# Reflow_Panel_Rev_F.net
KiCad netlist of a schematic drawn in EAGLE
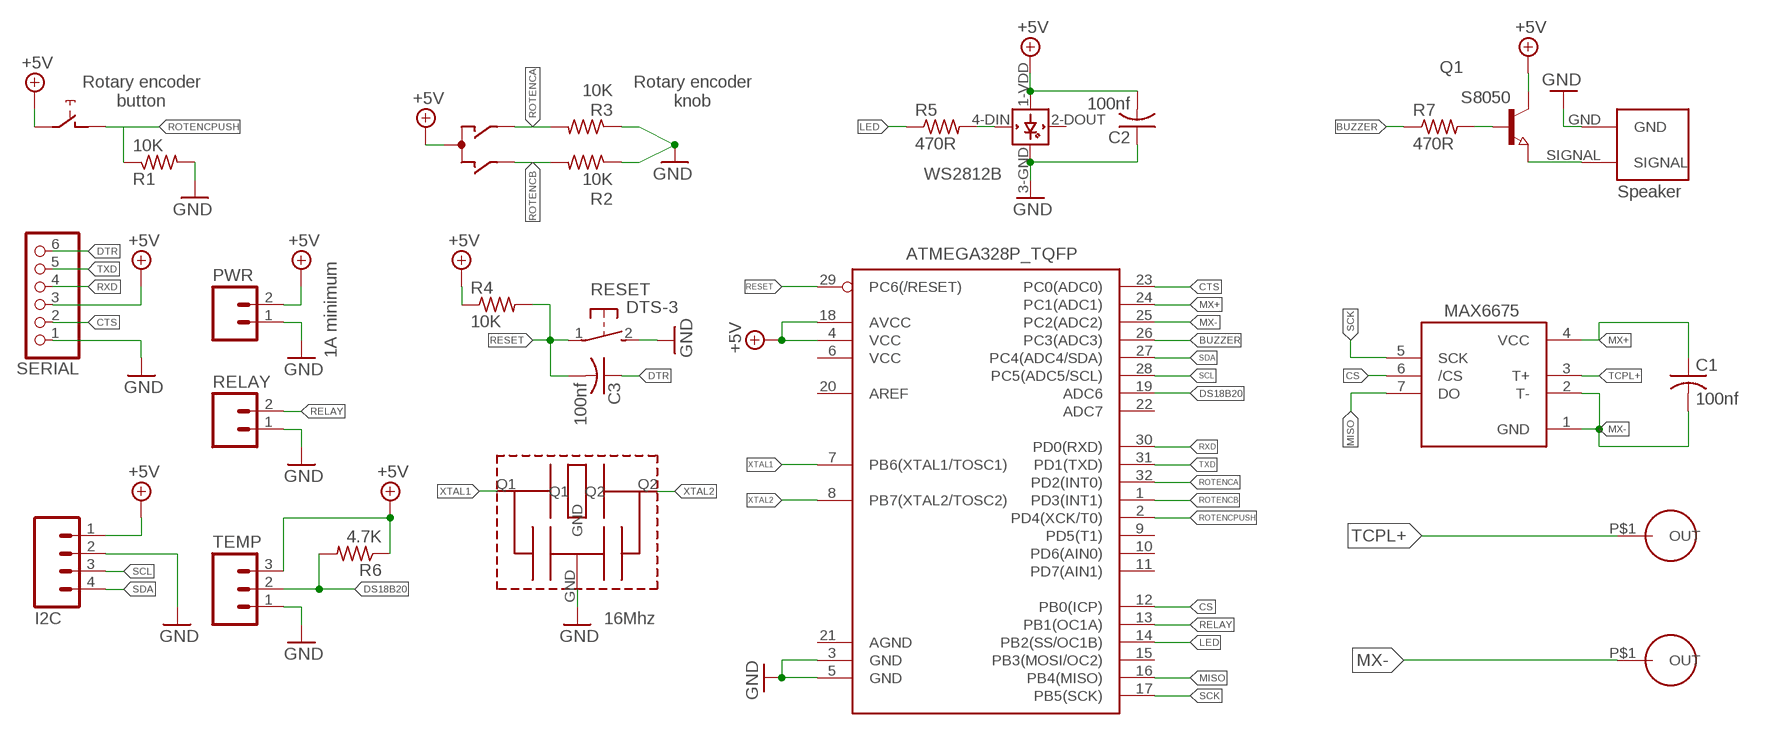
[diagram p0: schematic, sheet 1]

(export (version "E")
  (design (tool "Eeschema 10.0.6"))
  (components
    (comp (ref "C1")
      (value "100nf")
      (footprint "eagle-import:C0805")
      (libsource (lib "eagle-import") (part "C-USC0805"))
    )
    (comp (ref "C2")
      (value "100nf")
      (footprint "eagle-import:C0805")
      (libsource (lib "eagle-import") (part "C-USC0805"))
    )
    (comp (ref "C3")
      (value "100nf")
      (footprint "eagle-import:C0805")
      (libsource (lib "eagle-import") (part "C-USC0805"))
    )
    (comp (ref "I2C")
      (value "M04LOCK_LONGPADS")
      (footprint "eagle-import:1X04_LOCK_LONGPADS")
      (libsource (lib "eagle-import") (part "M04LOCK_LONGPADS"))
    )
    (comp (ref "IC2")
      (value "MAX6675")
      (footprint "eagle-import:SO08")
      (libsource (lib "eagle-import") (part "MAX6675"))
    )
    (comp (ref "L1")
      (value "WS2812B_")
      (footprint "eagle-import:WS2812B")
      (libsource (lib "eagle-import") (part "WS2812B_"))
    )
    (comp (ref "PWR")
      (value "M02LOCK")
      (footprint "eagle-import:1X02_LOCK")
      (libsource (lib "eagle-import") (part "M02LOCK"))
    )
    (comp (ref "Q1")
      (value "NPN-TRANSISTOR_SOT23")
      (footprint "eagle-import:SOT23")
      (libsource (lib "eagle-import") (part "NPN-TRANSISTOR_SOT23"))
    )
    (comp (ref "R1")
      (value "10K")
      (footprint "eagle-import:M0805")
      (libsource (lib "eagle-import") (part "R-US_M0805"))
    )
    (comp (ref "R2")
      (value "10K")
      (footprint "eagle-import:M0805")
      (libsource (lib "eagle-import") (part "R-US_M0805"))
    )
    (comp (ref "R3")
      (value "10K")
      (footprint "eagle-import:M0805")
      (libsource (lib "eagle-import") (part "R-US_M0805"))
    )
    (comp (ref "R4")
      (value "10K")
      (footprint "eagle-import:M0805")
      (libsource (lib "eagle-import") (part "R-US_M0805"))
    )
    (comp (ref "R5")
      (value "470R")
      (footprint "eagle-import:M0805")
      (libsource (lib "eagle-import") (part "R-US_M0805"))
    )
    (comp (ref "R6")
      (value "4.7K")
      (footprint "eagle-import:M0805")
      (libsource (lib "eagle-import") (part "R-US_M0805"))
    )
    (comp (ref "R7")
      (value "470R")
      (footprint "eagle-import:M0805")
      (libsource (lib "eagle-import") (part "R-US_M0805"))
    )
    (comp (ref "RELAY")
      (value "M02LOCK")
      (footprint "eagle-import:1X02_LOCK")
      (libsource (lib "eagle-import") (part "M02LOCK"))
    )
    (comp (ref "RESET")
      (value "DTS-3")
      (footprint "eagle-import:DTS-3")
      (libsource (lib "eagle-import") (part "DTS-3"))
    )
    (comp (ref "SERIAL")
      (value "PINHD-1X6LOCK")
      (footprint "eagle-import:1X06-BIGLOCK")
      (libsource (lib "eagle-import") (part "PINHD-1X6LOCK"))
    )
    (comp (ref "SW1")
      (value "EC12E_SW")
      (footprint "eagle-import:ALPS_EC12E_SW")
      (fields (field (name "MPN") "EC12E2424407"))
      (libsource (lib "eagle-import") (part "EC12E_SW"))
    )
    (comp (ref "TEMP")
      (value "M03LOCK")
      (footprint "eagle-import:1X03_LOCK")
      (libsource (lib "eagle-import") (part "M03LOCK"))
    )
    (comp (ref "U$1")
      (value "8.5MMSQUAREBUZZER")
      (footprint "eagle-import:8.5MMSQUAREBUZZER")
      (libsource (lib "eagle-import") (part "8.5MMSQUAREBUZZER"))
    )
    (comp (ref "U$2")
      (value "CSTCE16M0V53-R0")
      (footprint "eagle-import:CSTCE_V13C")
      (libsource (lib "eagle-import") (part "CSTCE16M0V53-R0"))
    )
    (comp (ref "U$3")
      (value "BANANAFEMAIL-10.8-5.7")
      (footprint "eagle-import:BANANAFEMALE-10.8-5.7")
      (libsource (lib "eagle-import") (part "BANANAFEMAIL-10.8-5.7"))
    )
    (comp (ref "U$4")
      (value "BANANAFEMAIL-10.8-5.7")
      (footprint "eagle-import:BANANAFEMALE-10.8-5.7")
      (libsource (lib "eagle-import") (part "BANANAFEMAIL-10.8-5.7"))
    )
    (comp (ref "U1")
      (value "ATMEGA328P_TQFP")
      (footprint "eagle-import:TQFP32-08")
      (libsource (lib "eagle-import") (part "ATMEGA328P_TQFP"))
    )
  )
  (nets
    (net (code "1") (name "+5V") (class "Default")
      (node (ref "C2") (pin "2") (pinfunction "2_2") (pintype "passive"))
      (node (ref "I2C") (pin "1") (pinfunction "1_1") (pintype "passive"))
      (node (ref "L1") (pin "1-VDD") (pinfunction "VDD_1-VDD") (pintype "bidirectional"))
      (node (ref "PWR") (pin "2") (pinfunction "2_2") (pintype "passive"))
      (node (ref "Q1") (pin "3") (pinfunction "C_3") (pintype "passive"))
      (node (ref "R4") (pin "1") (pinfunction "1_1") (pintype "passive"))
      (node (ref "R6") (pin "1") (pinfunction "1_1") (pintype "passive"))
      (node (ref "SERIAL") (pin "3") (pinfunction "3_3") (pintype "passive"))
      (node (ref "SW1") (pin "C") (pinfunction "C_C") (pintype "passive"))
      (node (ref "SW1") (pin "E") (pinfunction "2_E") (pintype "passive"))
      (node (ref "TEMP") (pin "3") (pinfunction "3_3") (pintype "passive"))
      (node (ref "U1") (pin "18") (pinfunction "AVCC_18") (pintype "bidirectional"))
      (node (ref "U1") (pin "4") (pinfunction "VCC_4") (pintype "bidirectional"))
    )
    (net (code "2") (name "BUZZER") (class "Default")
      (node (ref "R7") (pin "1") (pinfunction "1_1") (pintype "passive"))
      (node (ref "U1") (pin "26") (pinfunction "PC3(ADC3)_26") (pintype "bidirectional"))
    )
    (net (code "3") (name "CS") (class "Default")
      (node (ref "IC2") (pin "6") (pinfunction "/CS_6") (pintype "input"))
      (node (ref "U1") (pin "12") (pinfunction "PB0(ICP)_12") (pintype "bidirectional"))
    )
    (net (code "4") (name "CTS") (class "Default")
      (node (ref "SERIAL") (pin "2") (pinfunction "2_2") (pintype "passive"))
      (node (ref "U1") (pin "23") (pinfunction "PC0(ADC0)_23") (pintype "bidirectional"))
    )
    (net (code "5") (name "DS18B20") (class "Default")
      (node (ref "R6") (pin "2") (pinfunction "2_2") (pintype "passive"))
      (node (ref "TEMP") (pin "2") (pinfunction "2_2") (pintype "passive"))
      (node (ref "U1") (pin "19") (pinfunction "ADC6_19") (pintype "bidirectional"))
    )
    (net (code "6") (name "DTR") (class "Default")
      (node (ref "C3") (pin "1") (pinfunction "1_1") (pintype "passive"))
      (node (ref "SERIAL") (pin "6") (pinfunction "6_6") (pintype "passive"))
    )
    (net (code "7") (name "GND") (class "Default")
      (node (ref "C2") (pin "1") (pinfunction "1_1") (pintype "passive"))
      (node (ref "I2C") (pin "2") (pinfunction "2_2") (pintype "passive"))
      (node (ref "L1") (pin "3-GND") (pinfunction "GND_3-GND") (pintype "bidirectional"))
      (node (ref "PWR") (pin "1") (pinfunction "1_1") (pintype "passive"))
      (node (ref "R1") (pin "2") (pinfunction "2_2") (pintype "passive"))
      (node (ref "R2") (pin "1") (pinfunction "1_1") (pintype "passive"))
      (node (ref "R3") (pin "1") (pinfunction "1_1") (pintype "passive"))
      (node (ref "RELAY") (pin "1") (pinfunction "1_1") (pintype "passive"))
      (node (ref "RESET") (pin "2") (pinfunction "2_2") (pintype "passive"))
      (node (ref "SERIAL") (pin "1") (pinfunction "1_1") (pintype "passive"))
      (node (ref "TEMP") (pin "1") (pinfunction "1_1") (pintype "passive"))
      (node (ref "U$1") (pin "GND") (pinfunction "GND_GND") (pintype "bidirectional"))
      (node (ref "U$2") (pin "GND") (pinfunction "GND_GND") (pintype "bidirectional"))
      (node (ref "U1") (pin "3") (pinfunction "GND_3") (pintype "bidirectional"))
      (node (ref "U1") (pin "5") (pinfunction "GND_5") (pintype "bidirectional"))
    )
    (net (code "8") (name "LED") (class "Default")
      (node (ref "R5") (pin "1") (pinfunction "1_1") (pintype "passive"))
      (node (ref "U1") (pin "14") (pinfunction "PB2(SS/OC1B)_14") (pintype "bidirectional"))
    )
    (net (code "9") (name "MISO") (class "Default")
      (node (ref "IC2") (pin "7") (pinfunction "DO_7") (pintype "output"))
      (node (ref "U1") (pin "16") (pinfunction "PB4(MISO)_16") (pintype "bidirectional"))
    )
    (net (code "10") (name "MX+") (class "Default")
      (node (ref "C1") (pin "1") (pinfunction "1_1") (pintype "passive"))
      (node (ref "IC2") (pin "4") (pinfunction "VCC_4") (pintype "power_in"))
      (node (ref "U1") (pin "24") (pinfunction "PC1(ADC1)_24") (pintype "bidirectional"))
    )
    (net (code "11") (name "MX-") (class "Default")
      (node (ref "C1") (pin "2") (pinfunction "2_2") (pintype "passive"))
      (node (ref "IC2") (pin "1") (pinfunction "GND_1") (pintype "power_in"))
      (node (ref "IC2") (pin "2") (pinfunction "T-_2") (pintype "input"))
      (node (ref "U$3") (pin "P$1") (pinfunction "OUT_P$1") (pintype "bidirectional"))
      (node (ref "U1") (pin "25") (pinfunction "PC2(ADC2)_25") (pintype "bidirectional"))
    )
    (net (code "12") (name "Net-(L1-DIN)") (class "Default")
      (node (ref "L1") (pin "4-DIN") (pinfunction "DIN_4-DIN") (pintype "input"))
      (node (ref "R5") (pin "2") (pinfunction "2_2") (pintype "passive"))
    )
    (net (code "13") (name "Net-(Q1-B)") (class "Default")
      (node (ref "Q1") (pin "1") (pinfunction "B_1") (pintype "passive"))
      (node (ref "R7") (pin "2") (pinfunction "2_2") (pintype "passive"))
    )
    (net (code "14") (name "Net-(Q1-E)") (class "Default")
      (node (ref "Q1") (pin "2") (pinfunction "E_2") (pintype "passive"))
      (node (ref "U$1") (pin "SIGNAL") (pinfunction "SIGNAL_SIGNAL") (pintype "bidirectional"))
    )
    (net (code "15") (name "RELAY") (class "Default")
      (node (ref "RELAY") (pin "2") (pinfunction "2_2") (pintype "passive"))
      (node (ref "U1") (pin "13") (pinfunction "PB1(OC1A)_13") (pintype "bidirectional"))
    )
    (net (code "16") (name "RESET") (class "Default")
      (node (ref "C3") (pin "2") (pinfunction "2_2") (pintype "passive"))
      (node (ref "R4") (pin "2") (pinfunction "2_2") (pintype "passive"))
      (node (ref "RESET") (pin "1") (pinfunction "1_1") (pintype "passive"))
      (node (ref "U1") (pin "29") (pinfunction "PC6(/RESET)_29") (pintype "bidirectional"))
    )
    (net (code "17") (name "ROTENCA") (class "Default")
      (node (ref "R3") (pin "2") (pinfunction "2_2") (pintype "passive"))
      (node (ref "SW1") (pin "A") (pinfunction "A_A") (pintype "passive"))
      (node (ref "U1") (pin "32") (pinfunction "PD2(INT0)_32") (pintype "bidirectional"))
    )
    (net (code "18") (name "ROTENCB") (class "Default")
      (node (ref "R2") (pin "2") (pinfunction "2_2") (pintype "passive"))
      (node (ref "SW1") (pin "B") (pinfunction "B_B") (pintype "passive"))
      (node (ref "U1") (pin "1") (pinfunction "PD3(INT1)_1") (pintype "bidirectional"))
    )
    (net (code "19") (name "ROTENCPUSH") (class "Default")
      (node (ref "R1") (pin "1") (pinfunction "1_1") (pintype "passive"))
      (node (ref "SW1") (pin "D") (pinfunction "1_D") (pintype "passive"))
      (node (ref "U1") (pin "2") (pinfunction "PD4(XCK/T0)_2") (pintype "bidirectional"))
    )
    (net (code "20") (name "RXD") (class "Default")
      (node (ref "SERIAL") (pin "4") (pinfunction "4_4") (pintype "passive"))
      (node (ref "U1") (pin "30") (pinfunction "PD0(RXD)_30") (pintype "bidirectional"))
    )
    (net (code "21") (name "SCK") (class "Default")
      (node (ref "IC2") (pin "5") (pinfunction "SCK_5") (pintype "input"))
      (node (ref "U1") (pin "17") (pinfunction "PB5(SCK)_17") (pintype "bidirectional"))
    )
    (net (code "22") (name "SCL") (class "Default")
      (node (ref "I2C") (pin "3") (pinfunction "3_3") (pintype "passive"))
      (node (ref "U1") (pin "28") (pinfunction "PC5(ADC5/SCL)_28") (pintype "bidirectional"))
    )
    (net (code "23") (name "SDA") (class "Default")
      (node (ref "I2C") (pin "4") (pinfunction "4_4") (pintype "passive"))
      (node (ref "U1") (pin "27") (pinfunction "PC4(ADC4/SDA)_27") (pintype "bidirectional"))
    )
    (net (code "24") (name "TCPL+") (class "Default")
      (node (ref "IC2") (pin "3") (pinfunction "T+_3") (pintype "input"))
      (node (ref "U$4") (pin "P$1") (pinfunction "OUT_P$1") (pintype "bidirectional"))
    )
    (net (code "25") (name "TXD") (class "Default")
      (node (ref "SERIAL") (pin "5") (pinfunction "5_5") (pintype "passive"))
      (node (ref "U1") (pin "31") (pinfunction "PD1(TXD)_31") (pintype "bidirectional"))
    )
    (net (code "26") (name "XTAL1") (class "Default")
      (node (ref "U$2") (pin "Q1") (pinfunction "Q1_Q1") (pintype "bidirectional"))
      (node (ref "U1") (pin "7") (pinfunction "PB6(XTAL1/TOSC1)_7") (pintype "bidirectional"))
    )
    (net (code "27") (name "XTAL2") (class "Default")
      (node (ref "U$2") (pin "Q2") (pinfunction "Q2_Q2") (pintype "bidirectional"))
      (node (ref "U1") (pin "8") (pinfunction "PB7(XTAL2/TOSC2)_8") (pintype "bidirectional"))
    )
    (net (code "28") (name "unconnected-(L1-DOUT-Pad2-DOUT)") (class "Default")
      (node (ref "L1") (pin "2-DOUT") (pinfunction "DOUT_2-DOUT") (pintype "output"))
    )
    (net (code "29") (name "unconnected-(U1-ADC7-Pad22)") (class "Default")
      (node (ref "U1") (pin "22") (pinfunction "ADC7_22") (pintype "bidirectional"))
    )
    (net (code "30") (name "unconnected-(U1-AGND-Pad21)") (class "Default")
      (node (ref "U1") (pin "21") (pinfunction "AGND_21") (pintype "bidirectional"))
    )
    (net (code "31") (name "unconnected-(U1-AREF-Pad20)") (class "Default")
      (node (ref "U1") (pin "20") (pinfunction "AREF_20") (pintype "bidirectional"))
    )
    (net (code "32") (name "unconnected-(U1-PB3(MOSI{slash}OC2)-Pad15)") (class "Default")
      (node (ref "U1") (pin "15") (pinfunction "PB3(MOSI/OC2)_15") (pintype "bidirectional"))
    )
    (net (code "33") (name "unconnected-(U1-PD5(T1)-Pad9)") (class "Default")
      (node (ref "U1") (pin "9") (pinfunction "PD5(T1)_9") (pintype "bidirectional"))
    )
    (net (code "34") (name "unconnected-(U1-PD6(AIN0)-Pad10)") (class "Default")
      (node (ref "U1") (pin "10") (pinfunction "PD6(AIN0)_10") (pintype "bidirectional"))
    )
    (net (code "35") (name "unconnected-(U1-PD7(AIN1)-Pad11)") (class "Default")
      (node (ref "U1") (pin "11") (pinfunction "PD7(AIN1)_11") (pintype "bidirectional"))
    )
    (net (code "36") (name "unconnected-(U1-VCC-Pad6)") (class "Default")
      (node (ref "U1") (pin "6") (pinfunction "VCC_6") (pintype "bidirectional"))
    )
  )
)
